# camera_light_v1.net
KiCad netlist of a schematic drawn in EAGLE
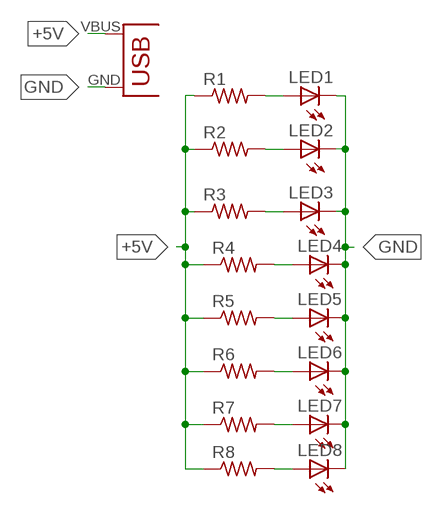
[diagram p0: schematic, sheet 1]

(export (version "E")
  (design (tool "Eeschema 10.0.6"))
  (components
    (comp (ref "LED1")
      (value "LED1210")
      (footprint "eagle-import:EIA1210")
      (libsource (lib "eagle-import") (part "LED1210"))
    )
    (comp (ref "LED2")
      (value "LED1210")
      (footprint "eagle-import:EIA1210")
      (libsource (lib "eagle-import") (part "LED1210"))
    )
    (comp (ref "LED3")
      (value "LED1210")
      (footprint "eagle-import:EIA1210")
      (libsource (lib "eagle-import") (part "LED1210"))
    )
    (comp (ref "LED4")
      (value "LED1210")
      (footprint "eagle-import:EIA1210")
      (libsource (lib "eagle-import") (part "LED1210"))
    )
    (comp (ref "LED5")
      (value "LED1210")
      (footprint "eagle-import:EIA1210")
      (libsource (lib "eagle-import") (part "LED1210"))
    )
    (comp (ref "LED6")
      (value "LED1210")
      (footprint "eagle-import:EIA1210")
      (libsource (lib "eagle-import") (part "LED1210"))
    )
    (comp (ref "LED7")
      (value "LED1210")
      (footprint "eagle-import:EIA1210")
      (libsource (lib "eagle-import") (part "LED1210"))
    )
    (comp (ref "LED8")
      (value "LED1210")
      (footprint "eagle-import:EIA1210")
      (libsource (lib "eagle-import") (part "LED1210"))
    )
    (comp (ref "R1")
      (value "RESISTOR0805")
      (footprint "eagle-import:R0805")
      (libsource (lib "eagle-import") (part "RESISTOR0805"))
    )
    (comp (ref "R2")
      (value "RESISTOR0805")
      (footprint "eagle-import:R0805")
      (libsource (lib "eagle-import") (part "RESISTOR0805"))
    )
    (comp (ref "R3")
      (value "RESISTOR0805")
      (footprint "eagle-import:R0805")
      (libsource (lib "eagle-import") (part "RESISTOR0805"))
    )
    (comp (ref "R4")
      (value "RESISTOR0805")
      (footprint "eagle-import:R0805")
      (libsource (lib "eagle-import") (part "RESISTOR0805"))
    )
    (comp (ref "R5")
      (value "RESISTOR0805")
      (footprint "eagle-import:R0805")
      (libsource (lib "eagle-import") (part "RESISTOR0805"))
    )
    (comp (ref "R6")
      (value "RESISTOR0805")
      (footprint "eagle-import:R0805")
      (libsource (lib "eagle-import") (part "RESISTOR0805"))
    )
    (comp (ref "R7")
      (value "RESISTOR0805")
      (footprint "eagle-import:R0805")
      (libsource (lib "eagle-import") (part "RESISTOR0805"))
    )
    (comp (ref "R8")
      (value "RESISTOR0805")
      (footprint "eagle-import:R0805")
      (libsource (lib "eagle-import") (part "RESISTOR0805"))
    )
    (comp (ref "U$1")
      (value "USB(POWER)")
      (footprint "eagle-import:USB(POWER)")
      (libsource (lib "eagle-import") (part "USB(POWER)"))
    )
  )
  (nets
    (net (code "1") (name "+5V") (class "Default")
      (node (ref "R1") (pin "1") (pinfunction "1_1") (pintype "passive"))
      (node (ref "R2") (pin "1") (pinfunction "1_1") (pintype "passive"))
      (node (ref "R3") (pin "1") (pinfunction "1_1") (pintype "passive"))
      (node (ref "R4") (pin "1") (pinfunction "1_1") (pintype "passive"))
      (node (ref "R5") (pin "1") (pinfunction "1_1") (pintype "passive"))
      (node (ref "R6") (pin "1") (pinfunction "1_1") (pintype "passive"))
      (node (ref "R7") (pin "1") (pinfunction "1_1") (pintype "passive"))
      (node (ref "R8") (pin "1") (pinfunction "1_1") (pintype "passive"))
      (node (ref "U$1") (pin "VBUS") (pinfunction "VCC_VBUS") (pintype "power_in"))
    )
    (net (code "2") (name "GND") (class "Default")
      (node (ref "LED1") (pin "CATHODE") (pinfunction "C_CATHODE") (pintype "passive"))
      (node (ref "LED2") (pin "CATHODE") (pinfunction "C_CATHODE") (pintype "passive"))
      (node (ref "LED3") (pin "CATHODE") (pinfunction "C_CATHODE") (pintype "passive"))
      (node (ref "LED4") (pin "CATHODE") (pinfunction "C_CATHODE") (pintype "passive"))
      (node (ref "LED5") (pin "CATHODE") (pinfunction "C_CATHODE") (pintype "passive"))
      (node (ref "LED6") (pin "CATHODE") (pinfunction "C_CATHODE") (pintype "passive"))
      (node (ref "LED7") (pin "CATHODE") (pinfunction "C_CATHODE") (pintype "passive"))
      (node (ref "LED8") (pin "CATHODE") (pinfunction "C_CATHODE") (pintype "passive"))
      (node (ref "U$1") (pin "GND") (pinfunction "GND_GND") (pintype "power_in"))
    )
    (net (code "3") (name "Net-(LED1-A)") (class "Default")
      (node (ref "LED1") (pin "ANODE") (pinfunction "A_ANODE") (pintype "passive"))
      (node (ref "R1") (pin "2") (pinfunction "2_2") (pintype "passive"))
    )
    (net (code "4") (name "Net-(LED2-A)") (class "Default")
      (node (ref "LED2") (pin "ANODE") (pinfunction "A_ANODE") (pintype "passive"))
      (node (ref "R2") (pin "2") (pinfunction "2_2") (pintype "passive"))
    )
    (net (code "5") (name "Net-(LED3-A)") (class "Default")
      (node (ref "LED3") (pin "ANODE") (pinfunction "A_ANODE") (pintype "passive"))
      (node (ref "R3") (pin "2") (pinfunction "2_2") (pintype "passive"))
    )
    (net (code "6") (name "Net-(LED4-A)") (class "Default")
      (node (ref "LED4") (pin "ANODE") (pinfunction "A_ANODE") (pintype "passive"))
      (node (ref "R4") (pin "2") (pinfunction "2_2") (pintype "passive"))
    )
    (net (code "7") (name "Net-(LED5-A)") (class "Default")
      (node (ref "LED5") (pin "ANODE") (pinfunction "A_ANODE") (pintype "passive"))
      (node (ref "R5") (pin "2") (pinfunction "2_2") (pintype "passive"))
    )
    (net (code "8") (name "Net-(LED6-A)") (class "Default")
      (node (ref "LED6") (pin "ANODE") (pinfunction "A_ANODE") (pintype "passive"))
      (node (ref "R6") (pin "2") (pinfunction "2_2") (pintype "passive"))
    )
    (net (code "9") (name "Net-(LED7-A)") (class "Default")
      (node (ref "LED7") (pin "ANODE") (pinfunction "A_ANODE") (pintype "passive"))
      (node (ref "R7") (pin "2") (pinfunction "2_2") (pintype "passive"))
    )
    (net (code "10") (name "Net-(LED8-A)") (class "Default")
      (node (ref "LED8") (pin "ANODE") (pinfunction "A_ANODE") (pintype "passive"))
      (node (ref "R8") (pin "2") (pinfunction "2_2") (pintype "passive"))
    )
  )
)
